# imu_logger.net
KiCad netlist of a schematic drawn in EAGLE
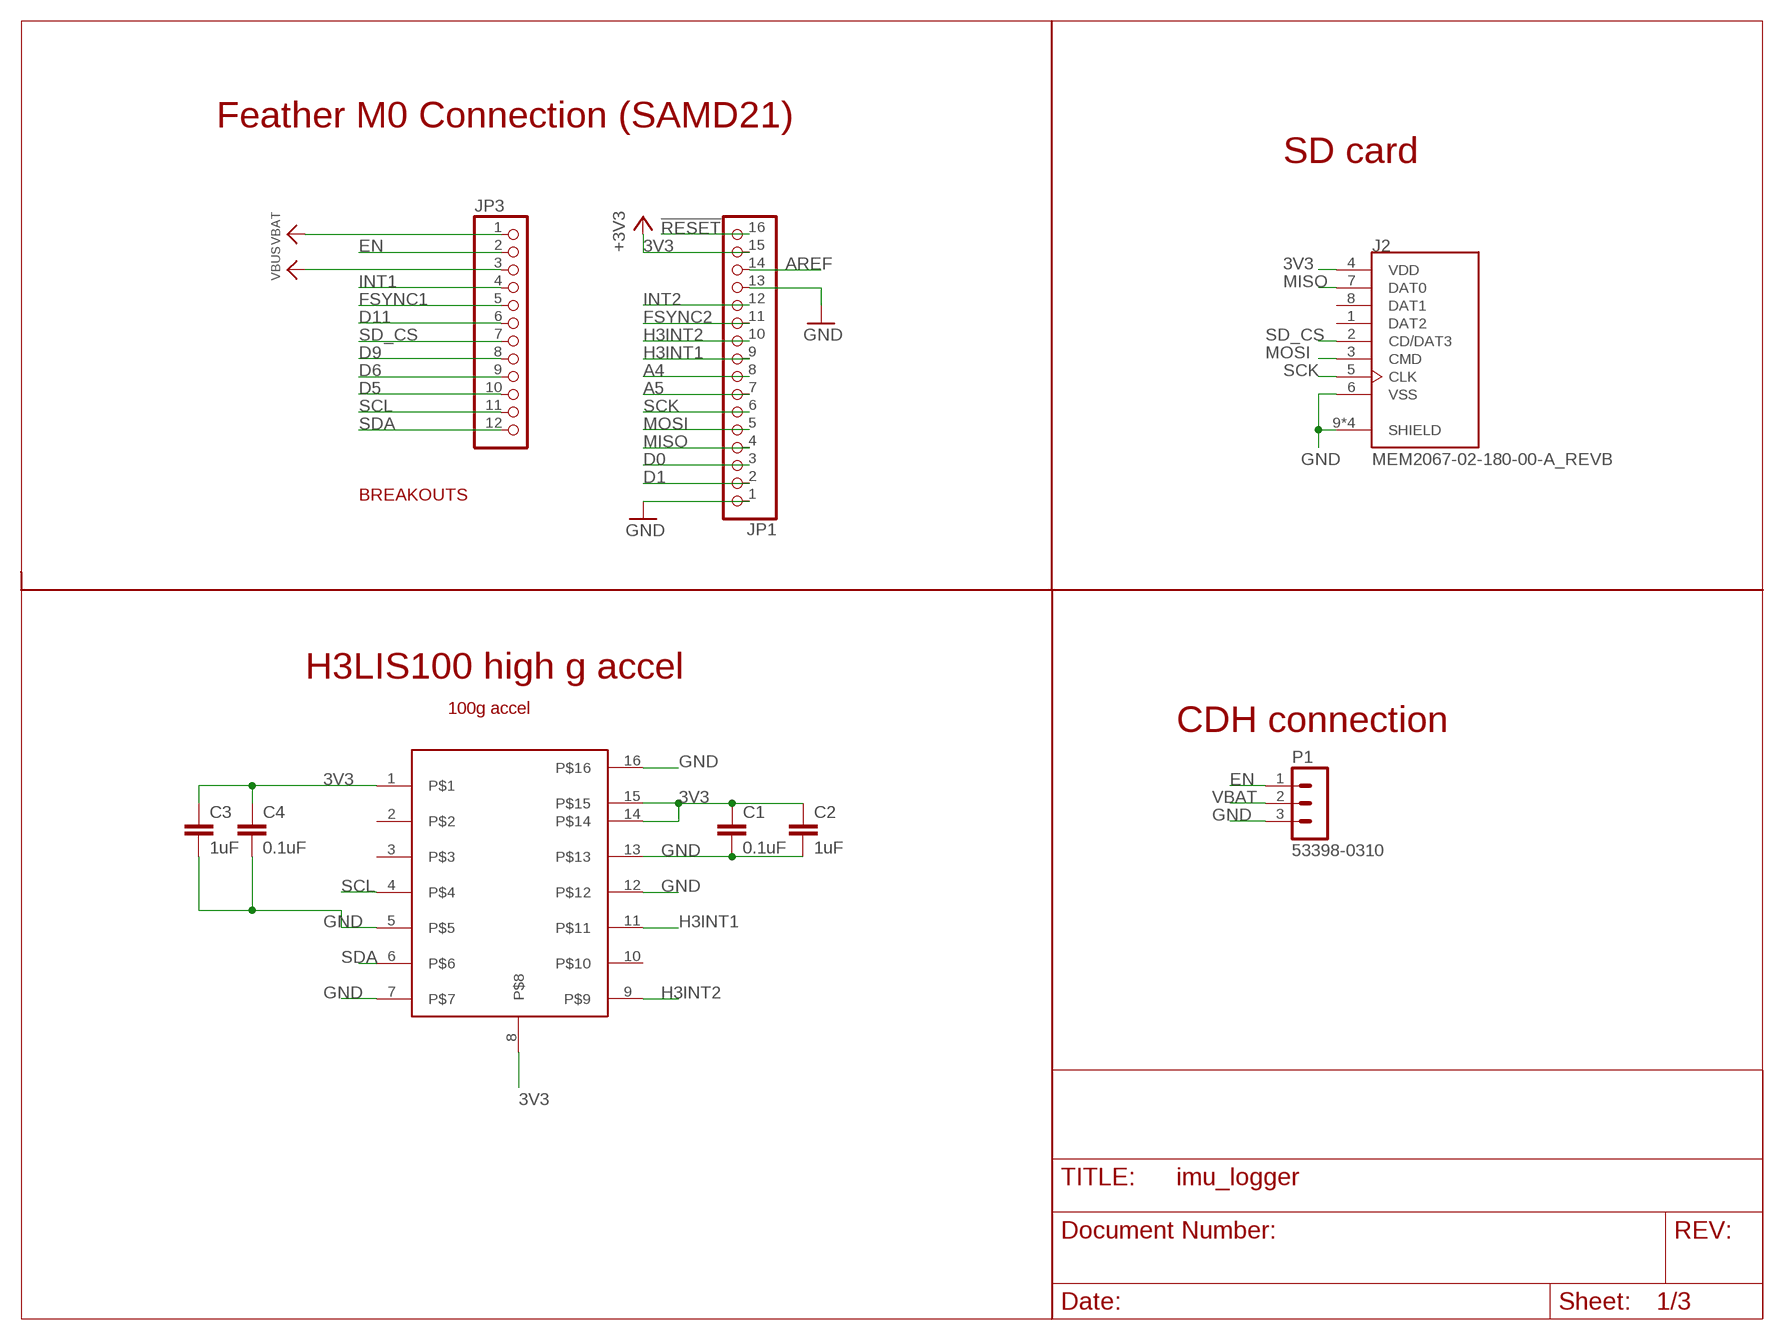
[diagram p0: schematic, sheet 1]
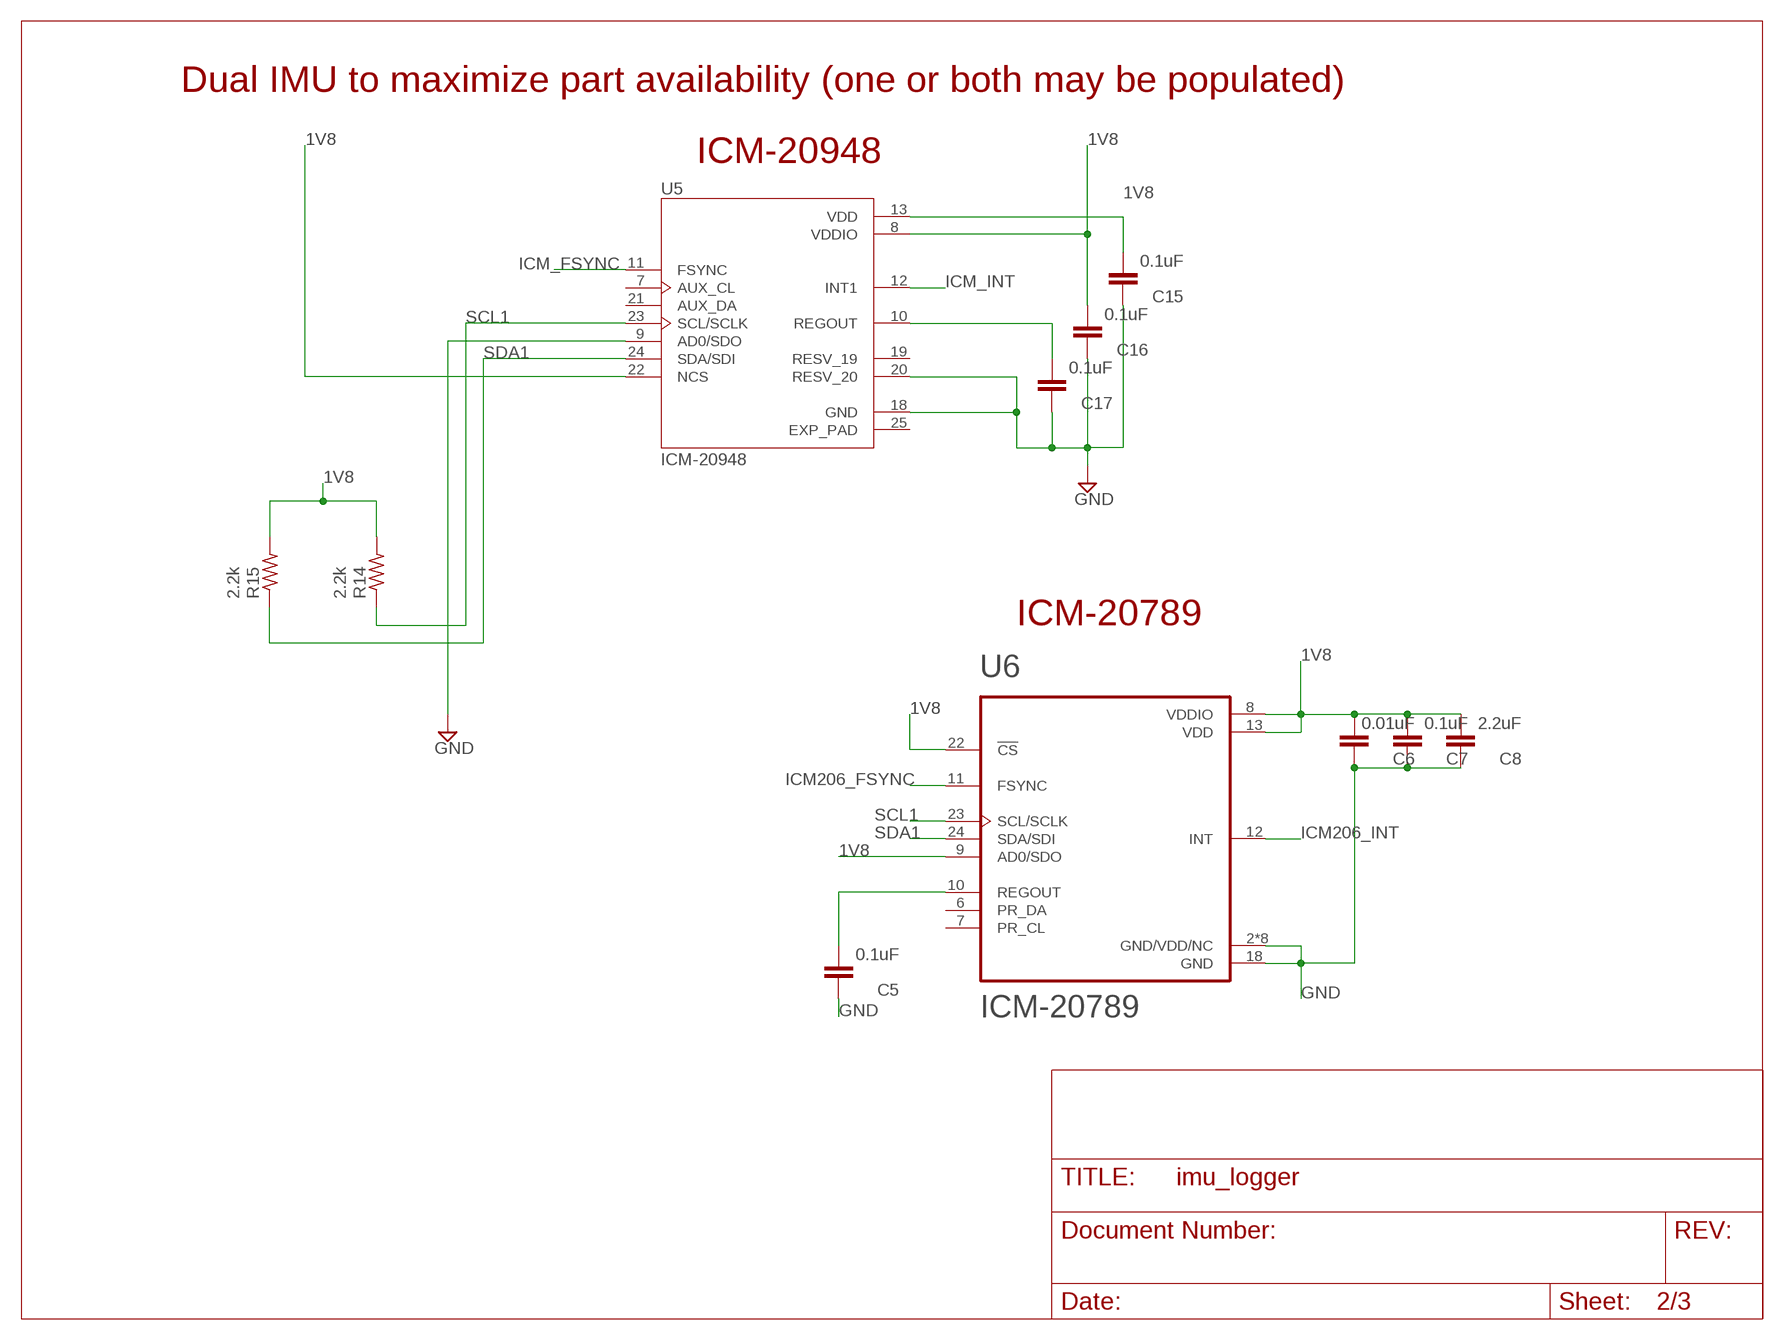
[diagram p1: schematic, sheet 2]
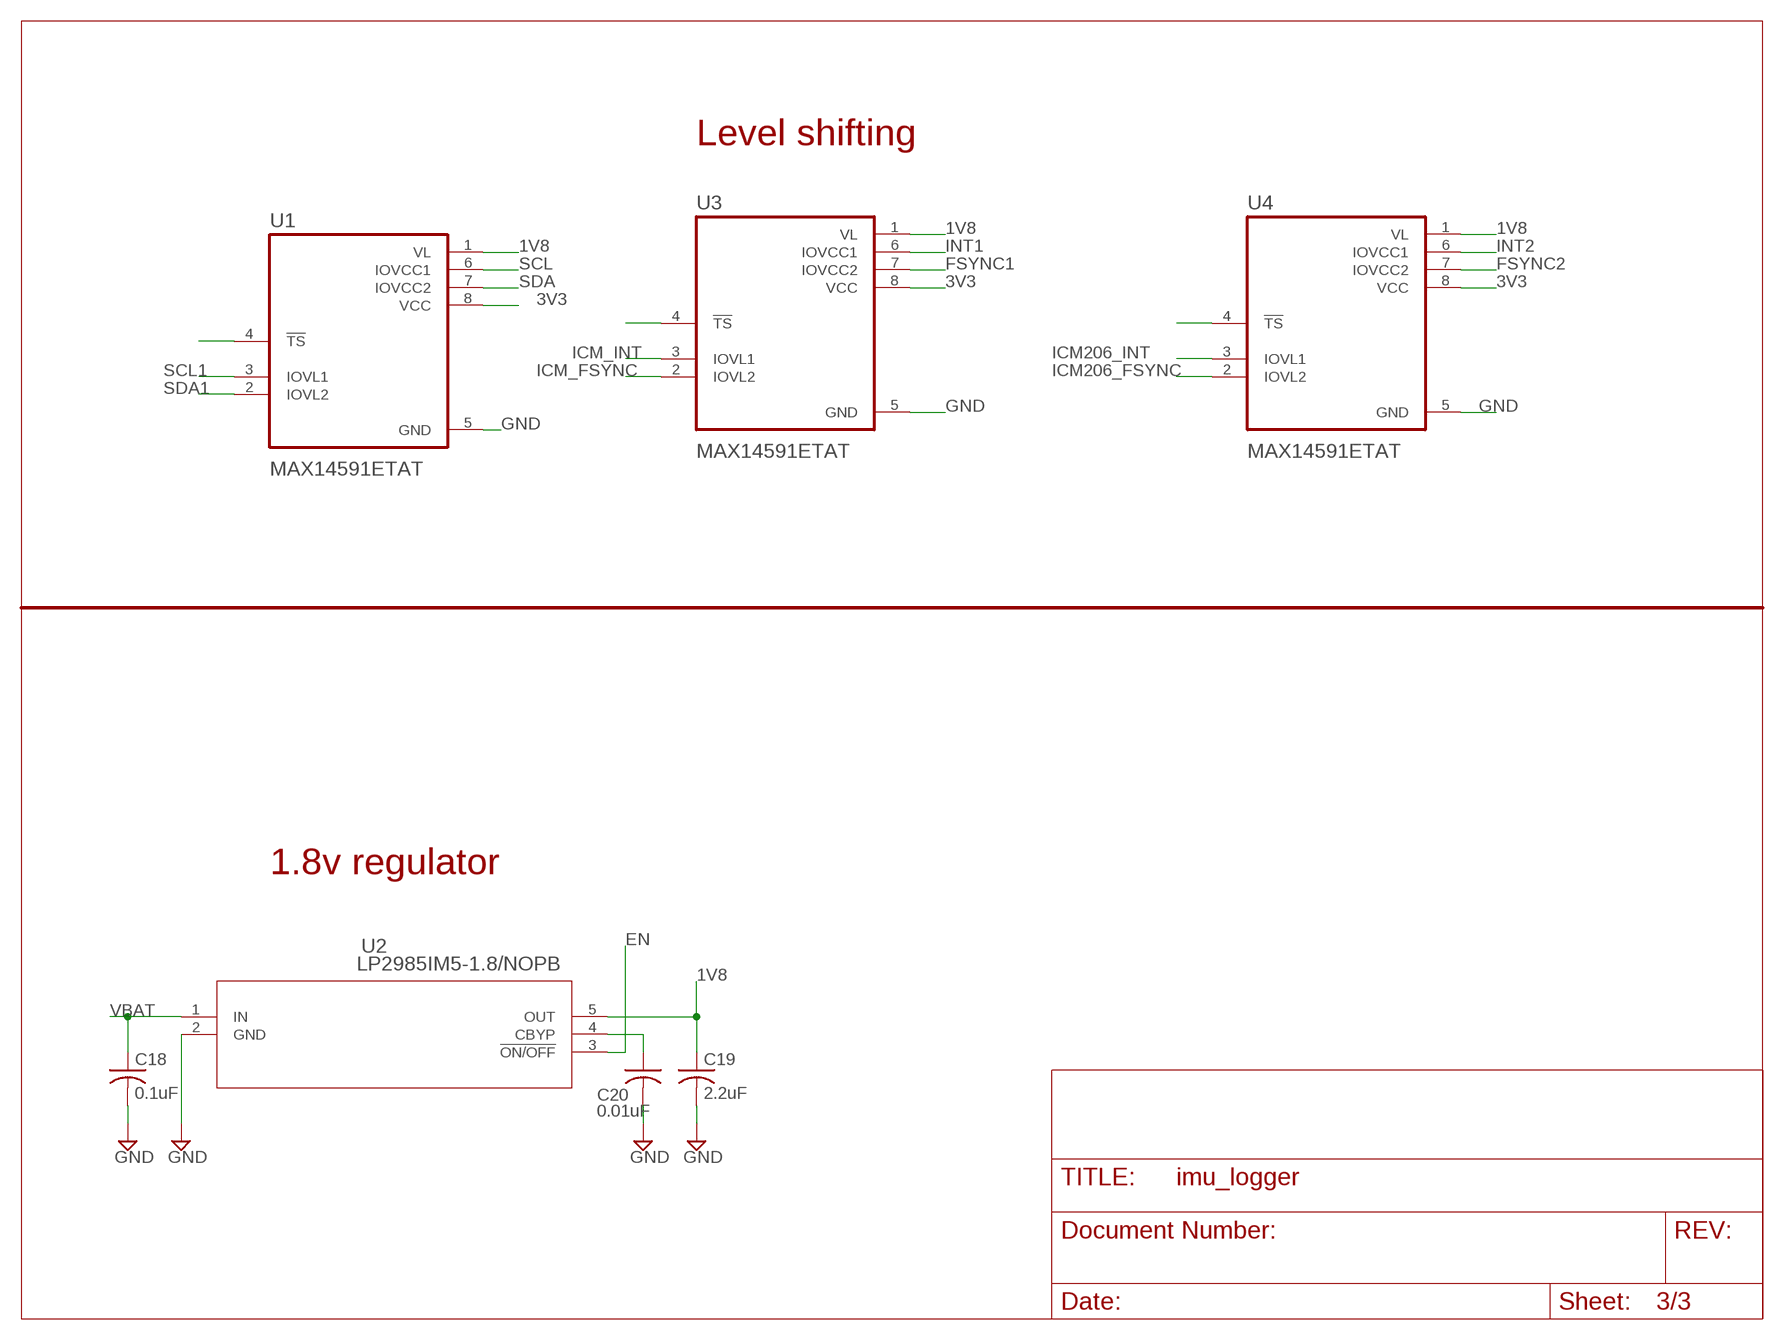
[diagram p2: schematic, sheet 3]

(export (version "E")
  (design (tool "Eeschema 10.0.6"))
  (components
    (comp (ref "C18")
      (value "0.1uF")
      (footprint "eagle-import:C0603")
      (libsource (lib "eagle-import") (part "C-USC0603"))
    )
    (comp (ref "C19")
      (value "2.2uF")
      (footprint "eagle-import:C0603")
      (libsource (lib "eagle-import") (part "C-USC0603"))
    )
    (comp (ref "C20")
      (value "0.01uF")
      (footprint "eagle-import:C0603")
      (libsource (lib "eagle-import") (part "C-USC0603"))
    )
    (comp (ref "U1")
      (value "MAX14591ETAT")
      (footprint "eagle-import:SON50P200X200X80-8N")
      (fields
        (field (name "DIGI-KEY_PART_NUMBER") "MAX14591ETA+TCT-ND")
        (field (name "MF") "Maxim Integrated")
        (field (name "MP") "MAX14591ETA+T")
      )
      (libsource (lib "eagle-import") (part "MAX14591ETAT"))
    )
    (comp (ref "U2")
      (value "LP2985IM5-1.8/NOPB")
      (footprint "eagle-import:MF05A")
      (fields (field (name "MANUFACTURER_PART_NUMBER") "LP2985IM51.8NOPB"))
      (libsource (lib "eagle-import") (part "LP2985IM5-1.8/NOPB"))
    )
    (comp (ref "U3")
      (value "MAX14591ETAT")
      (footprint "eagle-import:SON50P200X200X80-8N")
      (fields
        (field (name "DIGI-KEY_PART_NUMBER") "MAX14591ETA+TCT-ND")
        (field (name "MF") "Maxim Integrated")
        (field (name "MP") "MAX14591ETA+T")
      )
      (libsource (lib "eagle-import") (part "MAX14591ETAT"))
    )
    (comp (ref "U4")
      (value "MAX14591ETAT")
      (footprint "eagle-import:SON50P200X200X80-8N")
      (fields
        (field (name "DIGI-KEY_PART_NUMBER") "MAX14591ETA+TCT-ND")
        (field (name "MF") "Maxim Integrated")
        (field (name "MP") "MAX14591ETA+T")
      )
      (libsource (lib "eagle-import") (part "MAX14591ETAT"))
    )
    (comp (ref "C5")
      (value "0.1uF")
      (footprint "eagle-import:C0603")
      (libsource (lib "eagle-import") (part "C-EUC0603"))
    )
    (comp (ref "C6")
      (value "0.01uF")
      (footprint "eagle-import:C0603")
      (libsource (lib "eagle-import") (part "C-EUC0603"))
    )
    (comp (ref "C7")
      (value "0.1uF")
      (footprint "eagle-import:C0603")
      (libsource (lib "eagle-import") (part "C-EUC0603"))
    )
    (comp (ref "C8")
      (value "2.2uF")
      (footprint "eagle-import:C0603")
      (libsource (lib "eagle-import") (part "C-EUC0603"))
    )
    (comp (ref "C15")
      (value "0.1uF")
      (footprint "eagle-import:C0603")
      (libsource (lib "eagle-import") (part "C-EUC0603"))
    )
    (comp (ref "C16")
      (value "0.1uF")
      (footprint "eagle-import:C0603")
      (libsource (lib "eagle-import") (part "C-EUC0603"))
    )
    (comp (ref "C17")
      (value "0.1uF")
      (footprint "eagle-import:C0603")
      (libsource (lib "eagle-import") (part "C-EUC0603"))
    )
    (comp (ref "R14")
      (value "2.2k")
      (footprint "eagle-import:R0603")
      (libsource (lib "eagle-import") (part "R-US_R0603"))
    )
    (comp (ref "R15")
      (value "2.2k")
      (footprint "eagle-import:R0603")
      (libsource (lib "eagle-import") (part "R-US_R0603"))
    )
    (comp (ref "U5")
      (value "ICM-20948")
      (footprint "eagle-import:QFN40P300X300X105-25N")
      (fields (field (name "DIGI-KEY_PART_NUMBER") "1428-1123-1-ND") (field (name "MF") "TDK InvenSense"))
      (libsource (lib "eagle-import") (part "ICM-20948"))
    )
    (comp (ref "U6")
      (value "ICM-20789")
      (footprint "eagle-import:PQFN50P400X400X146-24N")
      (fields (field (name "DIGI-KEY_PART_NUMBER") "1428-1133-1-ND") (field (name "MF") "TDK InvenSense"))
      (libsource (lib "eagle-import") (part "ICM-20789"))
    )
    (comp (ref "C1")
      (value "0.1uF")
      (footprint "eagle-import:C0603")
      (libsource (lib "eagle-import") (part "C-EUC0603"))
    )
    (comp (ref "C2")
      (value "1uF")
      (footprint "eagle-import:C0603")
      (libsource (lib "eagle-import") (part "C-EUC0603"))
    )
    (comp (ref "C3")
      (value "1uF")
      (footprint "eagle-import:C0603")
      (libsource (lib "eagle-import") (part "C-EUC0603"))
    )
    (comp (ref "C4")
      (value "0.1uF")
      (footprint "eagle-import:C0603")
      (libsource (lib "eagle-import") (part "C-EUC0603"))
    )
    (comp (ref "J2")
      (value "MEM2067-02-180-00-A_REVB")
      (footprint "eagle-import:GCT_MEM2067-02-180-00-A_REVB")
      (fields (field (name "MF") "Global Connector Technology") (field (name "MP") "MEM2067-02-180-00-A"))
      (libsource (lib "eagle-import") (part "MEM2067-02-180-00-A_REVB"))
    )
    (comp (ref "JP1")
      (value "HEADER-1X16ROUND")
      (footprint "eagle-import:1X16_ROUND")
      (libsource (lib "eagle-import") (part "HEADER-1X16ROUND"))
    )
    (comp (ref "JP3")
      (value "HEADER-1X12")
      (footprint "eagle-import:1X12_ROUND")
      (libsource (lib "eagle-import") (part "HEADER-1X12"))
    )
    (comp (ref "P1")
      (value "53398-0310")
      (footprint "eagle-import:53398-0310")
      (libsource (lib "eagle-import") (part "53398-0310"))
    )
    (comp (ref "U$1")
      (value "H3LIS100DL")
      (footprint "eagle-import:XDCR_LIS3DHTR")
      (libsource (lib "eagle-import") (part "H3LIS100DL"))
    )
  )
  (nets
    (net (code "1") (name "1V8") (class "Default")
      (node (ref "C15") (pin "2") (pinfunction "2_2") (pintype "passive"))
      (node (ref "C16") (pin "2") (pinfunction "2_2") (pintype "passive"))
      (node (ref "C19") (pin "1") (pinfunction "1_1") (pintype "passive"))
      (node (ref "C6") (pin "2") (pinfunction "2_2") (pintype "passive"))
      (node (ref "C7") (pin "2") (pinfunction "2_2") (pintype "passive"))
      (node (ref "C8") (pin "2") (pinfunction "2_2") (pintype "passive"))
      (node (ref "R14") (pin "2") (pinfunction "2_2") (pintype "passive"))
      (node (ref "R15") (pin "2") (pinfunction "2_2") (pintype "passive"))
      (node (ref "U1") (pin "1") (pinfunction "VL_1") (pintype "power_in"))
      (node (ref "U2") (pin "5") (pinfunction "OUT_5") (pintype "power_in"))
      (node (ref "U3") (pin "1") (pinfunction "VL_1") (pintype "power_in"))
      (node (ref "U4") (pin "1") (pinfunction "VL_1") (pintype "power_in"))
      (node (ref "U5") (pin "13") (pinfunction "VDD_13") (pintype "power_in"))
      (node (ref "U5") (pin "22") (pinfunction "NCS_22") (pintype "input"))
      (node (ref "U5") (pin "8") (pinfunction "VDDIO_8") (pintype "power_in"))
      (node (ref "U6") (pin "13") (pinfunction "VDD_13") (pintype "power_in"))
      (node (ref "U6") (pin "22") (pinfunction "~{CS}_22") (pintype "input"))
      (node (ref "U6") (pin "8") (pinfunction "VDDIO_8") (pintype "power_in"))
      (node (ref "U6") (pin "9") (pinfunction "AD0/SDO_9") (pintype "bidirectional"))
    )
    (net (code "2") (name "3V3") (class "Default")
      (node (ref "C1") (pin "1") (pinfunction "1_1") (pintype "passive"))
      (node (ref "C2") (pin "1") (pinfunction "1_1") (pintype "passive"))
      (node (ref "C3") (pin "1") (pinfunction "1_1") (pintype "passive"))
      (node (ref "C4") (pin "1") (pinfunction "1_1") (pintype "passive"))
      (node (ref "J2") (pin "4") (pinfunction "VDD_4") (pintype "power_in"))
      (node (ref "JP1") (pin "15") (pinfunction "15_15") (pintype "passive"))
      (node (ref "U$1") (pin "1") (pinfunction "P$1_1") (pintype "bidirectional"))
      (node (ref "U$1") (pin "14") (pinfunction "P$14_14") (pintype "bidirectional"))
      (node (ref "U$1") (pin "15") (pinfunction "P$15_15") (pintype "bidirectional"))
      (node (ref "U$1") (pin "8") (pinfunction "P$8_8") (pintype "bidirectional"))
      (node (ref "U1") (pin "8") (pinfunction "VCC_8") (pintype "power_in"))
      (node (ref "U3") (pin "8") (pinfunction "VCC_8") (pintype "power_in"))
      (node (ref "U4") (pin "8") (pinfunction "VCC_8") (pintype "power_in"))
    )
    (net (code "3") (name "A4") (class "Default")
      (node (ref "JP1") (pin "8") (pinfunction "8_8") (pintype "passive"))
    )
    (net (code "4") (name "A5") (class "Default")
      (node (ref "JP1") (pin "7") (pinfunction "7_7") (pintype "passive"))
    )
    (net (code "5") (name "AREF") (class "Default")
      (node (ref "JP1") (pin "14") (pinfunction "14_14") (pintype "passive"))
    )
    (net (code "6") (name "D0") (class "Default")
      (node (ref "JP1") (pin "3") (pinfunction "3_3") (pintype "passive"))
    )
    (net (code "7") (name "D1") (class "Default")
      (node (ref "JP1") (pin "2") (pinfunction "2_2") (pintype "passive"))
    )
    (net (code "8") (name "D5") (class "Default")
      (node (ref "JP3") (pin "10") (pinfunction "10_10") (pintype "passive"))
    )
    (net (code "9") (name "D6") (class "Default")
      (node (ref "JP3") (pin "9") (pinfunction "9_9") (pintype "passive"))
    )
    (net (code "10") (name "D9") (class "Default")
      (node (ref "JP3") (pin "8") (pinfunction "8_8") (pintype "passive"))
    )
    (net (code "11") (name "D11") (class "Default")
      (node (ref "JP3") (pin "6") (pinfunction "6_6") (pintype "passive"))
    )
    (net (code "12") (name "EN") (class "Default")
      (node (ref "JP3") (pin "2") (pinfunction "2_2") (pintype "passive"))
      (node (ref "P1") (pin "1") (pinfunction "1_1") (pintype "passive"))
      (node (ref "U2") (pin "3") (pinfunction "~{ON/OFF}_3") (pintype "input"))
    )
    (net (code "13") (name "EXP_PAD") (class "Default")
      (node (ref "U5") (pin "25") (pinfunction "EXP_PAD_25") (pintype "power_in"))
    )
    (net (code "14") (name "FSYNC1") (class "Default")
      (node (ref "JP3") (pin "5") (pinfunction "5_5") (pintype "passive"))
      (node (ref "U3") (pin "7") (pinfunction "IOVCC2_7") (pintype "power_in"))
    )
    (net (code "15") (name "FSYNC2") (class "Default")
      (node (ref "JP1") (pin "11") (pinfunction "11_11") (pintype "passive"))
      (node (ref "U4") (pin "7") (pinfunction "IOVCC2_7") (pintype "power_in"))
    )
    (net (code "16") (name "GND") (class "Default")
      (node (ref "C1") (pin "2") (pinfunction "2_2") (pintype "passive"))
      (node (ref "C15") (pin "1") (pinfunction "1_1") (pintype "passive"))
      (node (ref "C16") (pin "1") (pinfunction "1_1") (pintype "passive"))
      (node (ref "C17") (pin "1") (pinfunction "1_1") (pintype "passive"))
      (node (ref "C18") (pin "2") (pinfunction "2_2") (pintype "passive"))
      (node (ref "C19") (pin "2") (pinfunction "2_2") (pintype "passive"))
      (node (ref "C2") (pin "2") (pinfunction "2_2") (pintype "passive"))
      (node (ref "C20") (pin "2") (pinfunction "2_2") (pintype "passive"))
      (node (ref "C3") (pin "2") (pinfunction "2_2") (pintype "passive"))
      (node (ref "C4") (pin "2") (pinfunction "2_2") (pintype "passive"))
      (node (ref "C5") (pin "1") (pinfunction "1_1") (pintype "passive"))
      (node (ref "C6") (pin "1") (pinfunction "1_1") (pintype "passive"))
      (node (ref "C7") (pin "1") (pinfunction "1_1") (pintype "passive"))
      (node (ref "C8") (pin "1") (pinfunction "1_1") (pintype "passive"))
      (node (ref "J2") (pin "10") (pinfunction "SHIELD_10") (pintype "passive"))
      (node (ref "J2") (pin "11") (pinfunction "SHIELD_11") (pintype "passive"))
      (node (ref "J2") (pin "12") (pinfunction "SHIELD_12") (pintype "passive"))
      (node (ref "J2") (pin "6") (pinfunction "VSS_6") (pintype "power_in"))
      (node (ref "J2") (pin "9") (pinfunction "SHIELD_9") (pintype "passive"))
      (node (ref "JP1") (pin "1") (pinfunction "1_1") (pintype "passive"))
      (node (ref "JP1") (pin "13") (pinfunction "13_13") (pintype "passive"))
      (node (ref "P1") (pin "3") (pinfunction "3_3") (pintype "passive"))
      (node (ref "U$1") (pin "12") (pinfunction "P$12_12") (pintype "bidirectional"))
      (node (ref "U$1") (pin "13") (pinfunction "P$13_13") (pintype "bidirectional"))
      (node (ref "U$1") (pin "16") (pinfunction "P$16_16") (pintype "bidirectional"))
      (node (ref "U$1") (pin "5") (pinfunction "P$5_5") (pintype "bidirectional"))
      (node (ref "U$1") (pin "7") (pinfunction "P$7_7") (pintype "bidirectional"))
      (node (ref "U1") (pin "5") (pinfunction "GND_5") (pintype "power_in"))
      (node (ref "U2") (pin "2") (pinfunction "GND_2") (pintype "power_in"))
      (node (ref "U3") (pin "5") (pinfunction "GND_5") (pintype "power_in"))
      (node (ref "U4") (pin "5") (pinfunction "GND_5") (pintype "power_in"))
      (node (ref "U5") (pin "18") (pinfunction "GND_18") (pintype "power_in"))
      (node (ref "U5") (pin "20") (pinfunction "RESV_20_20") (pintype "passive"))
      (node (ref "U5") (pin "9") (pinfunction "AD0/SDO_9") (pintype "output"))
      (node (ref "U6") (pin "14") (pinfunction "GND/VDD/NC_14") (pintype "power_in"))
      (node (ref "U6") (pin "15") (pinfunction "GND/VDD/NC_15") (pintype "power_in"))
      (node (ref "U6") (pin "16") (pinfunction "GND/VDD/NC_16") (pintype "power_in"))
      (node (ref "U6") (pin "17") (pinfunction "GND/VDD/NC_17") (pintype "power_in"))
      (node (ref "U6") (pin "18") (pinfunction "GND_18") (pintype "power_in"))
      (node (ref "U6") (pin "2") (pinfunction "GND/VDD/NC_2") (pintype "power_in"))
      (node (ref "U6") (pin "3") (pinfunction "GND/VDD/NC_3") (pintype "power_in"))
      (node (ref "U6") (pin "4") (pinfunction "GND/VDD/NC_4") (pintype "power_in"))
      (node (ref "U6") (pin "5") (pinfunction "GND/VDD/NC_5") (pintype "power_in"))
    )
    (net (code "17") (name "H3INT1") (class "Default")
      (node (ref "JP1") (pin "9") (pinfunction "9_9") (pintype "passive"))
      (node (ref "U$1") (pin "11") (pinfunction "P$11_11") (pintype "bidirectional"))
    )
    (net (code "18") (name "H3INT2") (class "Default")
      (node (ref "JP1") (pin "10") (pinfunction "10_10") (pintype "passive"))
      (node (ref "U$1") (pin "9") (pinfunction "P$9_9") (pintype "bidirectional"))
    )
    (net (code "19") (name "ICM206_FSYNC") (class "Default")
      (node (ref "U4") (pin "2") (pinfunction "IOVL2_2") (pintype "bidirectional"))
      (node (ref "U6") (pin "11") (pinfunction "FSYNC_11") (pintype "input"))
    )
    (net (code "20") (name "ICM206_INT") (class "Default")
      (node (ref "U4") (pin "3") (pinfunction "IOVL1_3") (pintype "bidirectional"))
      (node (ref "U6") (pin "12") (pinfunction "INT_12") (pintype "output"))
    )
    (net (code "21") (name "ICM_FSYNC") (class "Default")
      (node (ref "U3") (pin "2") (pinfunction "IOVL2_2") (pintype "bidirectional"))
      (node (ref "U5") (pin "11") (pinfunction "FSYNC_11") (pintype "input"))
    )
    (net (code "22") (name "ICM_INT") (class "Default")
      (node (ref "U3") (pin "3") (pinfunction "IOVL1_3") (pintype "bidirectional"))
      (node (ref "U5") (pin "12") (pinfunction "INT1_12") (pintype "output"))
    )
    (net (code "23") (name "INT1") (class "Default")
      (node (ref "JP3") (pin "4") (pinfunction "4_4") (pintype "passive"))
      (node (ref "U3") (pin "6") (pinfunction "IOVCC1_6") (pintype "power_in"))
    )
    (net (code "24") (name "INT2") (class "Default")
      (node (ref "JP1") (pin "12") (pinfunction "12_12") (pintype "passive"))
      (node (ref "U4") (pin "6") (pinfunction "IOVCC1_6") (pintype "power_in"))
    )
    (net (code "25") (name "MISO") (class "Default")
      (node (ref "J2") (pin "7") (pinfunction "DAT0_7") (pintype "bidirectional"))
      (node (ref "JP1") (pin "4") (pinfunction "4_4") (pintype "passive"))
    )
    (net (code "26") (name "MOSI") (class "Default")
      (node (ref "J2") (pin "3") (pinfunction "CMD_3") (pintype "bidirectional"))
      (node (ref "JP1") (pin "5") (pinfunction "5_5") (pintype "passive"))
    )
    (net (code "27") (name "Net-(U2-CBYP)") (class "Default")
      (node (ref "C20") (pin "1") (pinfunction "1_1") (pintype "passive"))
      (node (ref "U2") (pin "4") (pinfunction "CBYP_4") (pintype "passive"))
    )
    (net (code "28") (name "Net-(U5-REGOUT)") (class "Default")
      (node (ref "C17") (pin "2") (pinfunction "2_2") (pintype "passive"))
      (node (ref "U5") (pin "10") (pinfunction "REGOUT_10") (pintype "output"))
    )
    (net (code "29") (name "Net-(U6-REGOUT)") (class "Default")
      (node (ref "C5") (pin "2") (pinfunction "2_2") (pintype "passive"))
      (node (ref "U6") (pin "10") (pinfunction "REGOUT_10") (pintype "passive"))
    )
    (net (code "30") (name "SCK") (class "Default")
      (node (ref "J2") (pin "5") (pinfunction "CLK_5") (pintype "bidirectional"))
      (node (ref "JP1") (pin "6") (pinfunction "6_6") (pintype "passive"))
    )
    (net (code "31") (name "SCL") (class "Default")
      (node (ref "JP3") (pin "11") (pinfunction "11_11") (pintype "passive"))
      (node (ref "U$1") (pin "4") (pinfunction "P$4_4") (pintype "bidirectional"))
      (node (ref "U1") (pin "6") (pinfunction "IOVCC1_6") (pintype "power_in"))
    )
    (net (code "32") (name "SCL1") (class "Default")
      (node (ref "R14") (pin "1") (pinfunction "1_1") (pintype "passive"))
      (node (ref "U1") (pin "3") (pinfunction "IOVL1_3") (pintype "bidirectional"))
      (node (ref "U5") (pin "23") (pinfunction "SCL/SCLK_23") (pintype "input"))
      (node (ref "U6") (pin "23") (pinfunction "SCL/SCLK_23") (pintype "input"))
    )
    (net (code "33") (name "SDA") (class "Default")
      (node (ref "JP3") (pin "12") (pinfunction "12_12") (pintype "passive"))
      (node (ref "U$1") (pin "6") (pinfunction "P$6_6") (pintype "bidirectional"))
      (node (ref "U1") (pin "7") (pinfunction "IOVCC2_7") (pintype "power_in"))
    )
    (net (code "34") (name "SDA1") (class "Default")
      (node (ref "R15") (pin "1") (pinfunction "1_1") (pintype "passive"))
      (node (ref "U1") (pin "2") (pinfunction "IOVL2_2") (pintype "bidirectional"))
      (node (ref "U5") (pin "24") (pinfunction "SDA/SDI_24") (pintype "bidirectional"))
      (node (ref "U6") (pin "24") (pinfunction "SDA/SDI_24") (pintype "bidirectional"))
    )
    (net (code "35") (name "SD_CS") (class "Default")
      (node (ref "J2") (pin "2") (pinfunction "CD/DAT3_2") (pintype "bidirectional"))
      (node (ref "JP3") (pin "7") (pinfunction "7_7") (pintype "passive"))
    )
    (net (code "36") (name "VBAT") (class "Default")
      (node (ref "C18") (pin "1") (pinfunction "1_1") (pintype "passive"))
      (node (ref "JP3") (pin "1") (pinfunction "1_1") (pintype "passive"))
      (node (ref "P1") (pin "2") (pinfunction "2_2") (pintype "passive"))
      (node (ref "U2") (pin "1") (pinfunction "IN_1") (pintype "power_in"))
    )
    (net (code "37") (name "VBUS") (class "Default")
      (node (ref "JP3") (pin "3") (pinfunction "3_3") (pintype "passive"))
    )
    (net (code "38") (name "unconnected-(J2-DAT1-Pad8)") (class "Default")
      (node (ref "J2") (pin "8") (pinfunction "DAT1_8") (pintype "bidirectional"))
    )
    (net (code "39") (name "unconnected-(J2-DAT2-Pad1)") (class "Default")
      (node (ref "J2") (pin "1") (pinfunction "DAT2_1") (pintype "bidirectional"))
    )
    (net (code "40") (name "unconnected-(U$1-P$2-Pad2)") (class "Default")
      (node (ref "U$1") (pin "2") (pinfunction "P$2_2") (pintype "bidirectional"))
    )
    (net (code "41") (name "unconnected-(U$1-P$3-Pad3)") (class "Default")
      (node (ref "U$1") (pin "3") (pinfunction "P$3_3") (pintype "bidirectional"))
    )
    (net (code "42") (name "unconnected-(U$1-P$10-Pad10)") (class "Default")
      (node (ref "U$1") (pin "10") (pinfunction "P$10_10") (pintype "bidirectional"))
    )
    (net (code "43") (name "unconnected-(U1-~{TS}-Pad4)") (class "Default")
      (node (ref "U1") (pin "4") (pinfunction "~{TS}_4") (pintype "bidirectional"))
    )
    (net (code "44") (name "unconnected-(U3-~{TS}-Pad4)") (class "Default")
      (node (ref "U3") (pin "4") (pinfunction "~{TS}_4") (pintype "bidirectional"))
    )
    (net (code "45") (name "unconnected-(U4-~{TS}-Pad4)") (class "Default")
      (node (ref "U4") (pin "4") (pinfunction "~{TS}_4") (pintype "bidirectional"))
    )
    (net (code "46") (name "unconnected-(U5-AUX_CL-Pad7)") (class "Default")
      (node (ref "U5") (pin "7") (pinfunction "AUX_CL_7") (pintype "input"))
    )
    (net (code "47") (name "unconnected-(U5-AUX_DA-Pad21)") (class "Default")
      (node (ref "U5") (pin "21") (pinfunction "AUX_DA_21") (pintype "input"))
    )
    (net (code "48") (name "unconnected-(U5-RESV_19-Pad19)") (class "Default")
      (node (ref "U5") (pin "19") (pinfunction "RESV_19_19") (pintype "passive"))
    )
    (net (code "49") (name "unconnected-(U6-PR_CL-Pad7)") (class "Default")
      (node (ref "U6") (pin "7") (pinfunction "PR_CL_7") (pintype "bidirectional"))
    )
    (net (code "50") (name "unconnected-(U6-PR_DA-Pad6)") (class "Default")
      (node (ref "U6") (pin "6") (pinfunction "PR_DA_6") (pintype "bidirectional"))
    )
    (net (code "51") (name "~{RESET}") (class "Default")
      (node (ref "JP1") (pin "16") (pinfunction "16_16") (pintype "passive"))
    )
  )
)
